# W005B.net
KiCad netlist of a schematic drawn in EAGLE
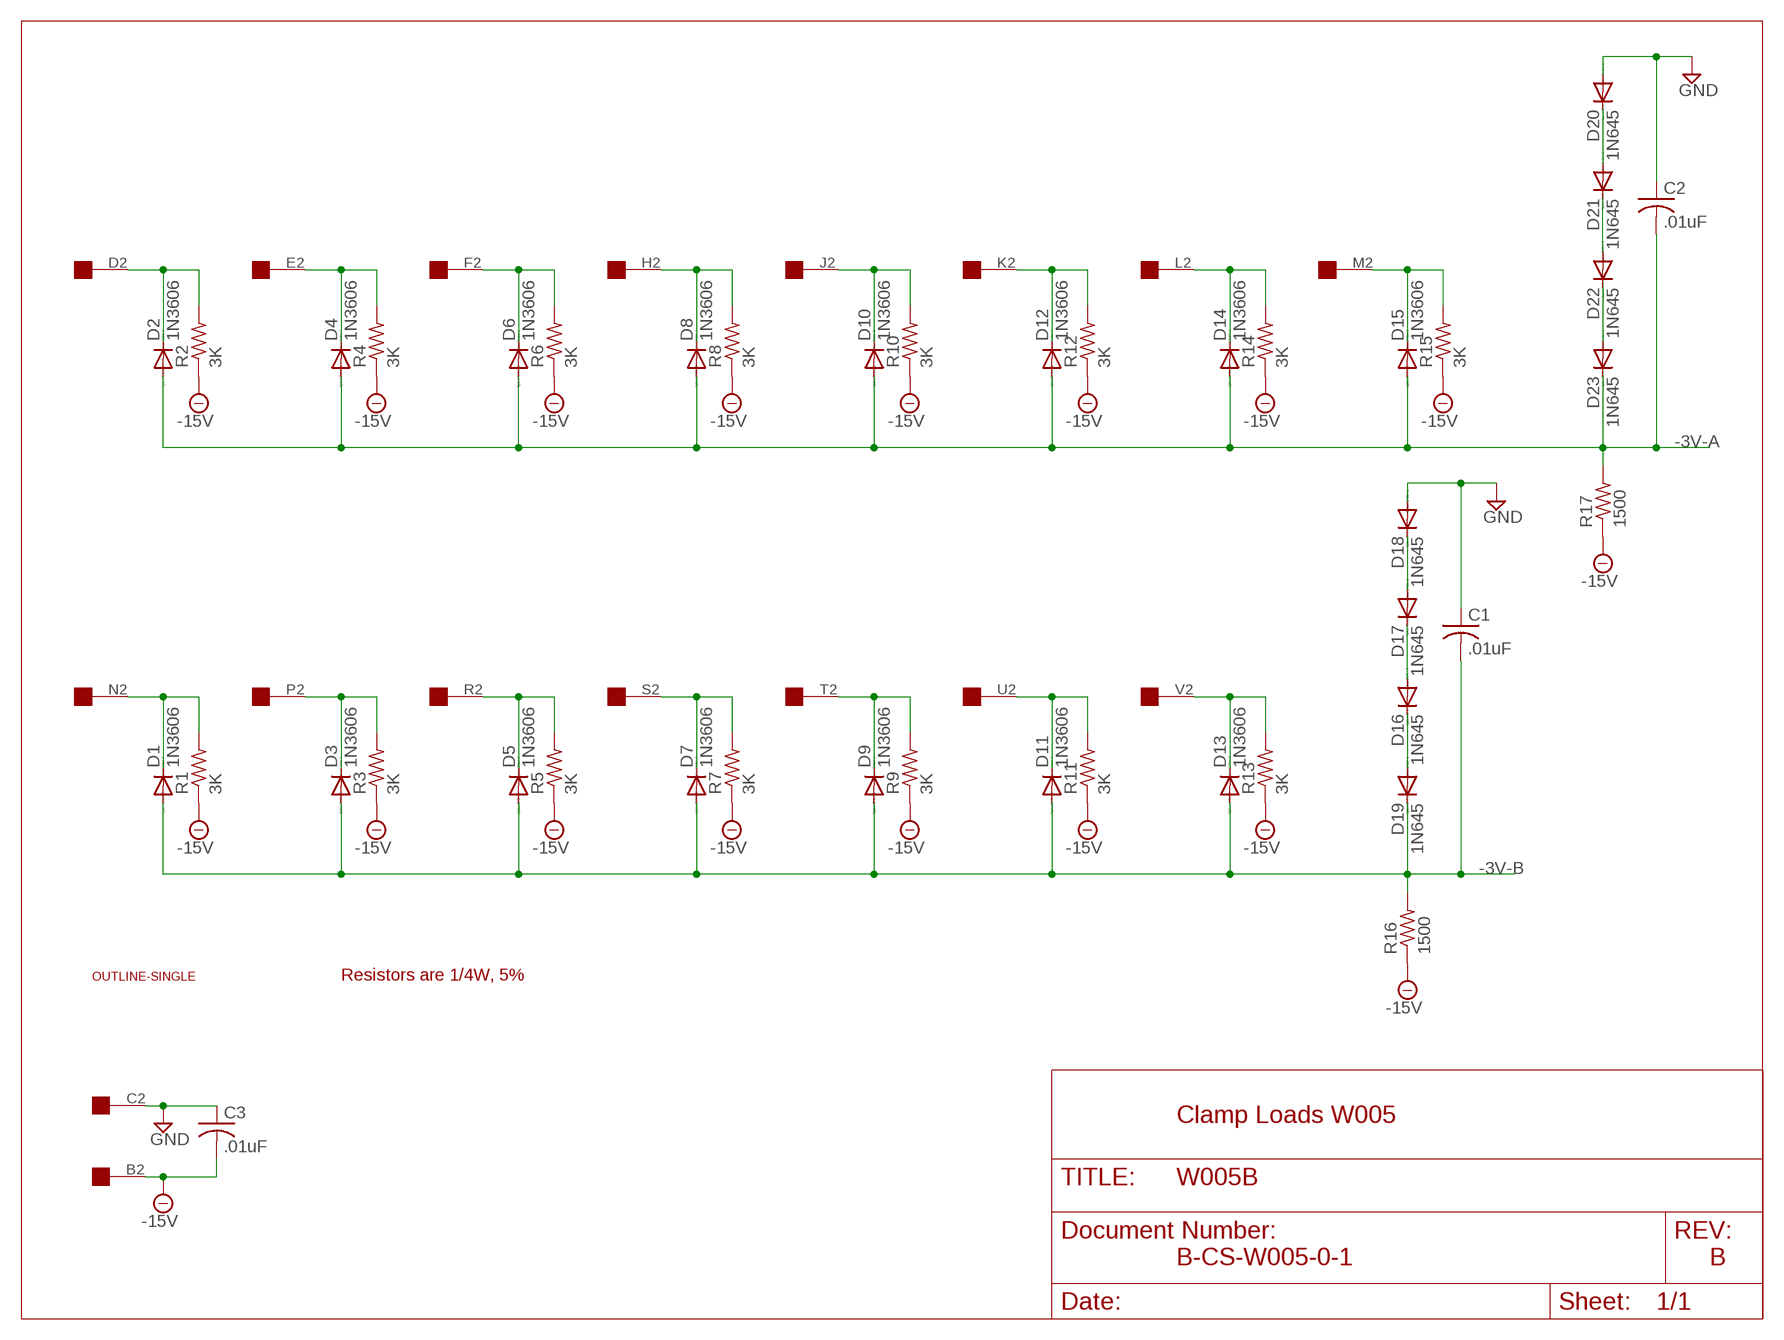
[diagram p0: schematic, sheet 1]

(export (version "E")
  (design (tool "Eeschema 10.0.6"))
  (components
    (comp (ref "C1")
      (value ".01uF")
      (footprint "eagle-import:C050-025X075")
      (libsource (lib "eagle-import") (part "C-US050-025X075"))
    )
    (comp (ref "C2")
      (value ".01uF")
      (footprint "eagle-import:C050-025X075")
      (libsource (lib "eagle-import") (part "C-US050-025X075"))
    )
    (comp (ref "C3")
      (value ".01uF")
      (footprint "eagle-import:C050-025X075")
      (libsource (lib "eagle-import") (part "C-US050-025X075"))
    )
    (comp (ref "D1")
      (value "1N3606")
      (footprint "eagle-import:DO35-10")
      (libsource (lib "eagle-import") (part "1N4148DO35-10"))
    )
    (comp (ref "D2")
      (value "1N3606")
      (footprint "eagle-import:DO35-10")
      (libsource (lib "eagle-import") (part "1N4148DO35-10"))
    )
    (comp (ref "D3")
      (value "1N3606")
      (footprint "eagle-import:DO35-10")
      (libsource (lib "eagle-import") (part "1N4148DO35-10"))
    )
    (comp (ref "D4")
      (value "1N3606")
      (footprint "eagle-import:DO35-10")
      (libsource (lib "eagle-import") (part "1N4148DO35-10"))
    )
    (comp (ref "D5")
      (value "1N3606")
      (footprint "eagle-import:DO35-10")
      (libsource (lib "eagle-import") (part "1N4148DO35-10"))
    )
    (comp (ref "D6")
      (value "1N3606")
      (footprint "eagle-import:DO35-10")
      (libsource (lib "eagle-import") (part "1N4148DO35-10"))
    )
    (comp (ref "D7")
      (value "1N3606")
      (footprint "eagle-import:DO35-10")
      (libsource (lib "eagle-import") (part "1N4148DO35-10"))
    )
    (comp (ref "D8")
      (value "1N3606")
      (footprint "eagle-import:DO35-10")
      (libsource (lib "eagle-import") (part "1N4148DO35-10"))
    )
    (comp (ref "D9")
      (value "1N3606")
      (footprint "eagle-import:DO35-10")
      (libsource (lib "eagle-import") (part "1N4148DO35-10"))
    )
    (comp (ref "D10")
      (value "1N3606")
      (footprint "eagle-import:DO35-10")
      (libsource (lib "eagle-import") (part "1N4148DO35-10"))
    )
    (comp (ref "D11")
      (value "1N3606")
      (footprint "eagle-import:DO35-10")
      (libsource (lib "eagle-import") (part "1N4148DO35-10"))
    )
    (comp (ref "D12")
      (value "1N3606")
      (footprint "eagle-import:DO35-10")
      (libsource (lib "eagle-import") (part "1N4148DO35-10"))
    )
    (comp (ref "D13")
      (value "1N3606")
      (footprint "eagle-import:DO35-10")
      (libsource (lib "eagle-import") (part "1N4148DO35-10"))
    )
    (comp (ref "D14")
      (value "1N3606")
      (footprint "eagle-import:DO35-10")
      (libsource (lib "eagle-import") (part "1N4148DO35-10"))
    )
    (comp (ref "D15")
      (value "1N3606")
      (footprint "eagle-import:DO35-10")
      (libsource (lib "eagle-import") (part "1N4148DO35-10"))
    )
    (comp (ref "D16")
      (value "1N645")
      (footprint "eagle-import:DO35-10")
      (libsource (lib "eagle-import") (part "1N4148DO35-10"))
    )
    (comp (ref "D17")
      (value "1N645")
      (footprint "eagle-import:DO35-10")
      (libsource (lib "eagle-import") (part "1N4148DO35-10"))
    )
    (comp (ref "D18")
      (value "1N645")
      (footprint "eagle-import:DO35-10")
      (libsource (lib "eagle-import") (part "1N4148DO35-10"))
    )
    (comp (ref "D19")
      (value "1N645")
      (footprint "eagle-import:DO35-10")
      (libsource (lib "eagle-import") (part "1N4148DO35-10"))
    )
    (comp (ref "D20")
      (value "1N645")
      (footprint "eagle-import:DO35-10")
      (libsource (lib "eagle-import") (part "1N4148DO35-10"))
    )
    (comp (ref "D21")
      (value "1N645")
      (footprint "eagle-import:DO35-10")
      (libsource (lib "eagle-import") (part "1N4148DO35-10"))
    )
    (comp (ref "D22")
      (value "1N645")
      (footprint "eagle-import:DO35-10")
      (libsource (lib "eagle-import") (part "1N4148DO35-10"))
    )
    (comp (ref "D23")
      (value "1N645")
      (footprint "eagle-import:DO35-10")
      (libsource (lib "eagle-import") (part "1N4148DO35-10"))
    )
    (comp (ref "R1")
      (value "3K")
      (footprint "eagle-import:0207_10")
      (libsource (lib "eagle-import") (part "R-US_0207/10"))
    )
    (comp (ref "R2")
      (value "3K")
      (footprint "eagle-import:0207_10")
      (libsource (lib "eagle-import") (part "R-US_0207/10"))
    )
    (comp (ref "R3")
      (value "3K")
      (footprint "eagle-import:0207_10")
      (libsource (lib "eagle-import") (part "R-US_0207/10"))
    )
    (comp (ref "R4")
      (value "3K")
      (footprint "eagle-import:0207_10")
      (libsource (lib "eagle-import") (part "R-US_0207/10"))
    )
    (comp (ref "R5")
      (value "3K")
      (footprint "eagle-import:0207_10")
      (libsource (lib "eagle-import") (part "R-US_0207/10"))
    )
    (comp (ref "R6")
      (value "3K")
      (footprint "eagle-import:0207_10")
      (libsource (lib "eagle-import") (part "R-US_0207/10"))
    )
    (comp (ref "R7")
      (value "3K")
      (footprint "eagle-import:0207_10")
      (libsource (lib "eagle-import") (part "R-US_0207/10"))
    )
    (comp (ref "R8")
      (value "3K")
      (footprint "eagle-import:0207_10")
      (libsource (lib "eagle-import") (part "R-US_0207/10"))
    )
    (comp (ref "R9")
      (value "3K")
      (footprint "eagle-import:0207_10")
      (libsource (lib "eagle-import") (part "R-US_0207/10"))
    )
    (comp (ref "R10")
      (value "3K")
      (footprint "eagle-import:0207_10")
      (libsource (lib "eagle-import") (part "R-US_0207/10"))
    )
    (comp (ref "R11")
      (value "3K")
      (footprint "eagle-import:0207_10")
      (libsource (lib "eagle-import") (part "R-US_0207/10"))
    )
    (comp (ref "R12")
      (value "3K")
      (footprint "eagle-import:0207_10")
      (libsource (lib "eagle-import") (part "R-US_0207/10"))
    )
    (comp (ref "R13")
      (value "3K")
      (footprint "eagle-import:0207_10")
      (libsource (lib "eagle-import") (part "R-US_0207/10"))
    )
    (comp (ref "R14")
      (value "3K")
      (footprint "eagle-import:0207_10")
      (libsource (lib "eagle-import") (part "R-US_0207/10"))
    )
    (comp (ref "R15")
      (value "3K")
      (footprint "eagle-import:0207_10")
      (libsource (lib "eagle-import") (part "R-US_0207/10"))
    )
    (comp (ref "R16")
      (value "1500")
      (footprint "eagle-import:0207_10")
      (libsource (lib "eagle-import") (part "R-US_0207/10"))
    )
    (comp (ref "R17")
      (value "1500")
      (footprint "eagle-import:0207_10")
      (libsource (lib "eagle-import") (part "R-US_0207/10"))
    )
    (comp (ref "U$1")
      (value "OUTLINE-SINGLE")
      (footprint "eagle-import:SINGLE")
      (libsource (lib "eagle-import") (part "OUTLINE-SINGLE"))
    )
    (comp (ref "U$2")
      (value "EDGE-1")
      (footprint "eagle-import:EDGE-CON1")
      (libsource (lib "eagle-import") (part "EDGE-1"))
    )
  )
  (nets
    (net (code "1") (name "-15V") (class "Default")
      (node (ref "C3") (pin "2") (pinfunction "2_2") (pintype "passive"))
      (node (ref "R1") (pin "1") (pinfunction "1_1") (pintype "passive"))
      (node (ref "R10") (pin "1") (pinfunction "1_1") (pintype "passive"))
      (node (ref "R11") (pin "1") (pinfunction "1_1") (pintype "passive"))
      (node (ref "R12") (pin "1") (pinfunction "1_1") (pintype "passive"))
      (node (ref "R13") (pin "1") (pinfunction "1_1") (pintype "passive"))
      (node (ref "R14") (pin "1") (pinfunction "1_1") (pintype "passive"))
      (node (ref "R15") (pin "1") (pinfunction "1_1") (pintype "passive"))
      (node (ref "R16") (pin "1") (pinfunction "1_1") (pintype "passive"))
      (node (ref "R17") (pin "1") (pinfunction "1_1") (pintype "passive"))
      (node (ref "R2") (pin "1") (pinfunction "1_1") (pintype "passive"))
      (node (ref "R3") (pin "1") (pinfunction "1_1") (pintype "passive"))
      (node (ref "R4") (pin "1") (pinfunction "1_1") (pintype "passive"))
      (node (ref "R5") (pin "1") (pinfunction "1_1") (pintype "passive"))
      (node (ref "R6") (pin "1") (pinfunction "1_1") (pintype "passive"))
      (node (ref "R7") (pin "1") (pinfunction "1_1") (pintype "passive"))
      (node (ref "R8") (pin "1") (pinfunction "1_1") (pintype "passive"))
      (node (ref "R9") (pin "1") (pinfunction "1_1") (pintype "passive"))
      (node (ref "U$2") (pin "B2") (pinfunction "1_B2") (pintype "bidirectional"))
    )
    (net (code "2") (name "/-3V-A") (class "Default")
      (node (ref "C2") (pin "2") (pinfunction "2_2") (pintype "passive"))
      (node (ref "D10") (pin "A") (pinfunction "A_A") (pintype "passive"))
      (node (ref "D12") (pin "A") (pinfunction "A_A") (pintype "passive"))
      (node (ref "D14") (pin "A") (pinfunction "A_A") (pintype "passive"))
      (node (ref "D15") (pin "A") (pinfunction "A_A") (pintype "passive"))
      (node (ref "D2") (pin "A") (pinfunction "A_A") (pintype "passive"))
      (node (ref "D23") (pin "C") (pinfunction "C_C") (pintype "passive"))
      (node (ref "D4") (pin "A") (pinfunction "A_A") (pintype "passive"))
      (node (ref "D6") (pin "A") (pinfunction "A_A") (pintype "passive"))
      (node (ref "D8") (pin "A") (pinfunction "A_A") (pintype "passive"))
      (node (ref "R17") (pin "2") (pinfunction "2_2") (pintype "passive"))
    )
    (net (code "3") (name "/-3V-B") (class "Default")
      (node (ref "C1") (pin "2") (pinfunction "2_2") (pintype "passive"))
      (node (ref "D1") (pin "A") (pinfunction "A_A") (pintype "passive"))
      (node (ref "D11") (pin "A") (pinfunction "A_A") (pintype "passive"))
      (node (ref "D13") (pin "A") (pinfunction "A_A") (pintype "passive"))
      (node (ref "D19") (pin "C") (pinfunction "C_C") (pintype "passive"))
      (node (ref "D3") (pin "A") (pinfunction "A_A") (pintype "passive"))
      (node (ref "D5") (pin "A") (pinfunction "A_A") (pintype "passive"))
      (node (ref "D7") (pin "A") (pinfunction "A_A") (pintype "passive"))
      (node (ref "D9") (pin "A") (pinfunction "A_A") (pintype "passive"))
      (node (ref "R16") (pin "2") (pinfunction "2_2") (pintype "passive"))
    )
    (net (code "4") (name "GND") (class "Default")
      (node (ref "C1") (pin "1") (pinfunction "1_1") (pintype "passive"))
      (node (ref "C2") (pin "1") (pinfunction "1_1") (pintype "passive"))
      (node (ref "C3") (pin "1") (pinfunction "1_1") (pintype "passive"))
      (node (ref "D18") (pin "A") (pinfunction "A_A") (pintype "passive"))
      (node (ref "D20") (pin "A") (pinfunction "A_A") (pintype "passive"))
      (node (ref "U$2") (pin "C2") (pinfunction "1_C2") (pintype "bidirectional"))
    )
    (net (code "5") (name "Net-(D16-PadA)") (class "Default")
      (node (ref "D16") (pin "A") (pinfunction "A_A") (pintype "passive"))
      (node (ref "D17") (pin "C") (pinfunction "C_C") (pintype "passive"))
    )
    (net (code "6") (name "Net-(D16-PadC)") (class "Default")
      (node (ref "D16") (pin "C") (pinfunction "C_C") (pintype "passive"))
      (node (ref "D19") (pin "A") (pinfunction "A_A") (pintype "passive"))
    )
    (net (code "7") (name "Net-(D17-PadA)") (class "Default")
      (node (ref "D17") (pin "A") (pinfunction "A_A") (pintype "passive"))
      (node (ref "D18") (pin "C") (pinfunction "C_C") (pintype "passive"))
    )
    (net (code "8") (name "Net-(D20-PadC)") (class "Default")
      (node (ref "D20") (pin "C") (pinfunction "C_C") (pintype "passive"))
      (node (ref "D21") (pin "A") (pinfunction "A_A") (pintype "passive"))
    )
    (net (code "9") (name "Net-(D21-PadC)") (class "Default")
      (node (ref "D21") (pin "C") (pinfunction "C_C") (pintype "passive"))
      (node (ref "D22") (pin "A") (pinfunction "A_A") (pintype "passive"))
    )
    (net (code "10") (name "Net-(D22-PadC)") (class "Default")
      (node (ref "D22") (pin "C") (pinfunction "C_C") (pintype "passive"))
      (node (ref "D23") (pin "A") (pinfunction "A_A") (pintype "passive"))
    )
    (net (code "11") (name "Net-(U$2D-1)") (class "Default")
      (node (ref "D2") (pin "C") (pinfunction "C_C") (pintype "passive"))
      (node (ref "R2") (pin "2") (pinfunction "2_2") (pintype "passive"))
      (node (ref "U$2") (pin "D2") (pinfunction "1_D2") (pintype "bidirectional"))
    )
    (net (code "12") (name "Net-(U$2E-1)") (class "Default")
      (node (ref "D4") (pin "C") (pinfunction "C_C") (pintype "passive"))
      (node (ref "R4") (pin "2") (pinfunction "2_2") (pintype "passive"))
      (node (ref "U$2") (pin "E2") (pinfunction "1_E2") (pintype "bidirectional"))
    )
    (net (code "13") (name "Net-(U$2F-1)") (class "Default")
      (node (ref "D6") (pin "C") (pinfunction "C_C") (pintype "passive"))
      (node (ref "R6") (pin "2") (pinfunction "2_2") (pintype "passive"))
      (node (ref "U$2") (pin "F2") (pinfunction "1_F2") (pintype "bidirectional"))
    )
    (net (code "14") (name "Net-(U$2G-1)") (class "Default")
      (node (ref "D8") (pin "C") (pinfunction "C_C") (pintype "passive"))
      (node (ref "R8") (pin "2") (pinfunction "2_2") (pintype "passive"))
      (node (ref "U$2") (pin "H2") (pinfunction "1_H2") (pintype "bidirectional"))
    )
    (net (code "15") (name "Net-(U$2H-1)") (class "Default")
      (node (ref "D10") (pin "C") (pinfunction "C_C") (pintype "passive"))
      (node (ref "R10") (pin "2") (pinfunction "2_2") (pintype "passive"))
      (node (ref "U$2") (pin "J2") (pinfunction "1_J2") (pintype "bidirectional"))
    )
    (net (code "16") (name "Net-(U$2I-1)") (class "Default")
      (node (ref "D12") (pin "C") (pinfunction "C_C") (pintype "passive"))
      (node (ref "R12") (pin "2") (pinfunction "2_2") (pintype "passive"))
      (node (ref "U$2") (pin "K2") (pinfunction "1_K2") (pintype "bidirectional"))
    )
    (net (code "17") (name "Net-(U$2J-1)") (class "Default")
      (node (ref "D14") (pin "C") (pinfunction "C_C") (pintype "passive"))
      (node (ref "R14") (pin "2") (pinfunction "2_2") (pintype "passive"))
      (node (ref "U$2") (pin "L2") (pinfunction "1_L2") (pintype "bidirectional"))
    )
    (net (code "18") (name "Net-(U$2K-1)") (class "Default")
      (node (ref "D15") (pin "C") (pinfunction "C_C") (pintype "passive"))
      (node (ref "R15") (pin "2") (pinfunction "2_2") (pintype "passive"))
      (node (ref "U$2") (pin "M2") (pinfunction "1_M2") (pintype "bidirectional"))
    )
    (net (code "19") (name "Net-(U$2L-1)") (class "Default")
      (node (ref "D1") (pin "C") (pinfunction "C_C") (pintype "passive"))
      (node (ref "R1") (pin "2") (pinfunction "2_2") (pintype "passive"))
      (node (ref "U$2") (pin "N2") (pinfunction "1_N2") (pintype "bidirectional"))
    )
    (net (code "20") (name "Net-(U$2M-1)") (class "Default")
      (node (ref "D3") (pin "C") (pinfunction "C_C") (pintype "passive"))
      (node (ref "R3") (pin "2") (pinfunction "2_2") (pintype "passive"))
      (node (ref "U$2") (pin "P2") (pinfunction "1_P2") (pintype "bidirectional"))
    )
    (net (code "21") (name "Net-(U$2N-1)") (class "Default")
      (node (ref "D5") (pin "C") (pinfunction "C_C") (pintype "passive"))
      (node (ref "R5") (pin "2") (pinfunction "2_2") (pintype "passive"))
      (node (ref "U$2") (pin "R2") (pinfunction "1_R2") (pintype "bidirectional"))
    )
    (net (code "22") (name "Net-(U$2O-1)") (class "Default")
      (node (ref "D7") (pin "C") (pinfunction "C_C") (pintype "passive"))
      (node (ref "R7") (pin "2") (pinfunction "2_2") (pintype "passive"))
      (node (ref "U$2") (pin "S2") (pinfunction "1_S2") (pintype "bidirectional"))
    )
    (net (code "23") (name "Net-(U$2P-1)") (class "Default")
      (node (ref "D9") (pin "C") (pinfunction "C_C") (pintype "passive"))
      (node (ref "R9") (pin "2") (pinfunction "2_2") (pintype "passive"))
      (node (ref "U$2") (pin "T2") (pinfunction "1_T2") (pintype "bidirectional"))
    )
    (net (code "24") (name "Net-(U$2Q-1)") (class "Default")
      (node (ref "D11") (pin "C") (pinfunction "C_C") (pintype "passive"))
      (node (ref "R11") (pin "2") (pinfunction "2_2") (pintype "passive"))
      (node (ref "U$2") (pin "U2") (pinfunction "1_U2") (pintype "bidirectional"))
    )
    (net (code "25") (name "Net-(U$2R-1)") (class "Default")
      (node (ref "D13") (pin "C") (pinfunction "C_C") (pintype "passive"))
      (node (ref "R13") (pin "2") (pinfunction "2_2") (pintype "passive"))
      (node (ref "U$2") (pin "V2") (pinfunction "1_V2") (pintype "bidirectional"))
    )
  )
)
